# Standalone_Kaleidoscope_8085_POWER_SUPPL.net
KiCad netlist of a schematic drawn in EAGLE
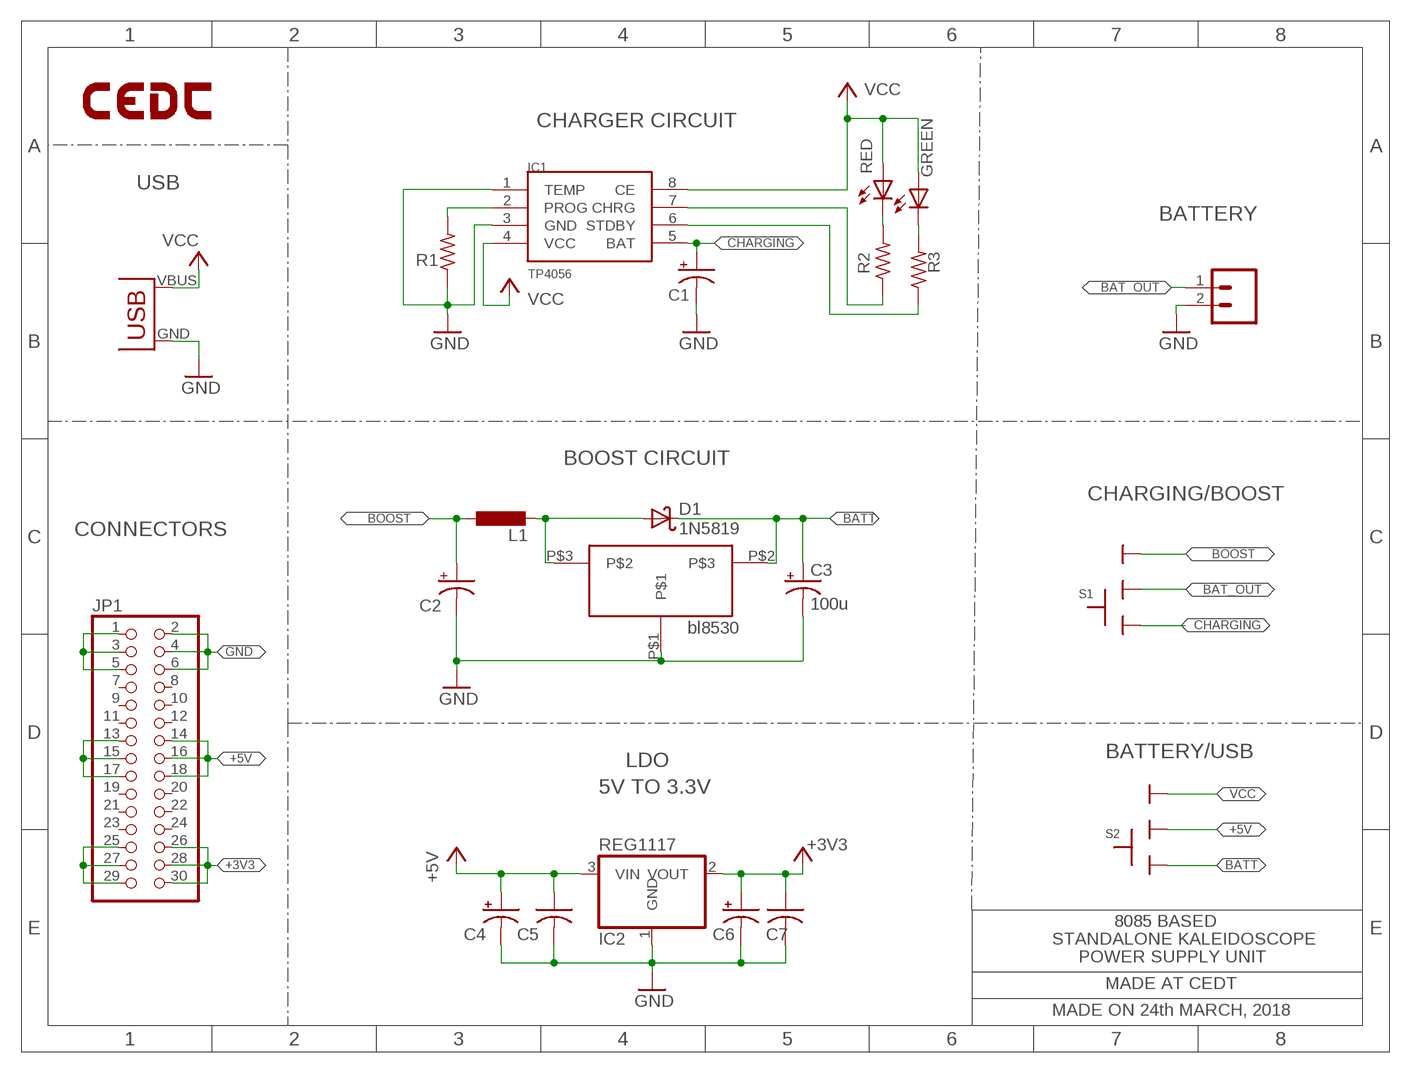
[diagram p0: schematic, sheet 1]

(export (version "E")
  (design (tool "Eeschema 10.0.6"))
  (components
    (comp (ref "BATTERY")
      (value "M02")
      (footprint "eagle-import:02P")
      (libsource (lib "eagle-import") (part "M02"))
    )
    (comp (ref "BL8530")
      (value "BL8530_5V")
      (footprint "eagle-import:BL8530_5V")
      (libsource (lib "eagle-import") (part "BL8530_5V"))
    )
    (comp (ref "C1")
      (value "10u")
      (footprint "eagle-import:C_6032-28R")
      (libsource (lib "eagle-import") (part "CAP_POL_10V"))
    )
    (comp (ref "C2")
      (value "10u")
      (footprint "eagle-import:C_6032-28R")
      (libsource (lib "eagle-import") (part "CAP_POL_10V"))
    )
    (comp (ref "C3")
      (value "100u")
      (footprint "eagle-import:C_6032-28R")
      (libsource (lib "eagle-import") (part "CEDT_JANUARY_2015_v7_CAP_POL_10V"))
    )
    (comp (ref "C4")
      (value "10u")
      (footprint "eagle-import:C_6032-28R")
      (libsource (lib "eagle-import") (part "CAP_POL_10V"))
    )
    (comp (ref "C5")
      (value "0.1u")
      (footprint "eagle-import:C0805")
      (libsource (lib "eagle-import") (part "CAP0805"))
    )
    (comp (ref "C6")
      (value "10u")
      (footprint "eagle-import:C_6032-28R")
      (libsource (lib "eagle-import") (part "CAP_POL_10V"))
    )
    (comp (ref "C7")
      (value "0.1u")
      (footprint "eagle-import:C0805")
      (libsource (lib "eagle-import") (part "CAP0805"))
    )
    (comp (ref "D1")
      (value "1N5819")
      (footprint "eagle-import:DO41-10")
      (libsource (lib "eagle-import") (part "1N5819"))
    )
    (comp (ref "GREEN")
      (value "LED3MM")
      (footprint "eagle-import:LED3MM")
      (libsource (lib "eagle-import") (part "LED3MM"))
    )
    (comp (ref "IC1")
      (value "TP4056")
      (footprint "eagle-import:SOP-8")
      (libsource (lib "eagle-import") (part "TP4056"))
    )
    (comp (ref "IC2")
      (value "REG1117")
      (footprint "eagle-import:SOT223")
      (libsource (lib "eagle-import") (part "REG1117"))
    )
    (comp (ref "JP1")
      (value "PINHD-2X15")
      (footprint "eagle-import:2X15")
      (libsource (lib "eagle-import") (part "PINHD-2X15"))
    )
    (comp (ref "L1")
      (value "47uH")
      (footprint "eagle-import:L4532P")
      (libsource (lib "eagle-import") (part "L-EUL4532P"))
    )
    (comp (ref "LOGO1")
      (value "LOGO-CEDTBOT-18MM")
      (footprint "eagle-import:LOGO-CEDT-BOT-18MM")
      (libsource (lib "eagle-import") (part "LOGO-CEDTBOT-18MM"))
    )
    (comp (ref "R1")
      (value "RESISTOR0805")
      (footprint "eagle-import:R0805")
      (libsource (lib "eagle-import") (part "RESISTOR0805"))
    )
    (comp (ref "R2")
      (value "470")
      (footprint "eagle-import:R0805")
      (libsource (lib "eagle-import") (part "RESISTOR0805"))
    )
    (comp (ref "R3")
      (value "470")
      (footprint "eagle-import:R0805")
      (libsource (lib "eagle-import") (part "RESISTOR0805"))
    )
    (comp (ref "RED")
      (value "LED3MM")
      (footprint "eagle-import:LED3MM")
      (libsource (lib "eagle-import") (part "LED3MM"))
    )
    (comp (ref "S1")
      (value "SLIDESWITCH-BIG")
      (footprint "eagle-import:BIGSWITCH")
      (libsource (lib "eagle-import") (part "SLIDESWITCH-BIG"))
    )
    (comp (ref "S2")
      (value "SLIDESWITCH-BIG")
      (footprint "eagle-import:BIGSWITCH")
      (libsource (lib "eagle-import") (part "SLIDESWITCH-BIG"))
    )
    (comp (ref "U$1")
      (value "USB(POWER)")
      (footprint "eagle-import:USB(POWER)")
      (libsource (lib "eagle-import") (part "USB(POWER)"))
    )
  )
  (nets
    (net (code "1") (name "+3V3") (class "Default")
      (node (ref "C6") (pin "+") (pinfunction "+_+") (pintype "passive"))
      (node (ref "C7") (pin "1") (pinfunction "1_1") (pintype "passive"))
      (node (ref "IC2") (pin "2") (pinfunction "VOUT_2") (pintype "output"))
      (node (ref "JP1") (pin "25") (pinfunction "25_25") (pintype "passive"))
      (node (ref "JP1") (pin "26") (pinfunction "26_26") (pintype "passive"))
      (node (ref "JP1") (pin "27") (pinfunction "27_27") (pintype "passive"))
      (node (ref "JP1") (pin "28") (pinfunction "28_28") (pintype "passive"))
      (node (ref "JP1") (pin "29") (pinfunction "29_29") (pintype "passive"))
      (node (ref "JP1") (pin "30") (pinfunction "30_30") (pintype "passive"))
    )
    (net (code "2") (name "+5V") (class "Default")
      (node (ref "C4") (pin "+") (pinfunction "+_+") (pintype "passive"))
      (node (ref "C5") (pin "1") (pinfunction "1_1") (pintype "passive"))
      (node (ref "IC2") (pin "3") (pinfunction "VIN_3") (pintype "input"))
      (node (ref "JP1") (pin "13") (pinfunction "13_13") (pintype "passive"))
      (node (ref "JP1") (pin "14") (pinfunction "14_14") (pintype "passive"))
      (node (ref "JP1") (pin "15") (pinfunction "15_15") (pintype "passive"))
      (node (ref "JP1") (pin "16") (pinfunction "16_16") (pintype "passive"))
      (node (ref "JP1") (pin "17") (pinfunction "17_17") (pintype "passive"))
      (node (ref "JP1") (pin "18") (pinfunction "18_18") (pintype "passive"))
      (node (ref "S2") (pin "2") (pinfunction "2_2") (pintype "bidirectional"))
    )
    (net (code "3") (name "/BATT") (class "Default")
      (node (ref "BL8530") (pin "P$2") (pinfunction "P$3_P$2") (pintype "bidirectional"))
      (node (ref "C3") (pin "+") (pinfunction "+_+") (pintype "passive"))
      (node (ref "D1") (pin "C") (pinfunction "C_C") (pintype "passive"))
      (node (ref "S2") (pin "1") (pinfunction "1_1") (pintype "bidirectional"))
    )
    (net (code "4") (name "/BAT_OUT") (class "Default")
      (node (ref "BATTERY") (pin "1") (pinfunction "1_1") (pintype "passive"))
      (node (ref "S1") (pin "2") (pinfunction "2_2") (pintype "bidirectional"))
    )
    (net (code "5") (name "/BOOST") (class "Default")
      (node (ref "C2") (pin "+") (pinfunction "+_+") (pintype "passive"))
      (node (ref "L1") (pin "1") (pinfunction "1_1") (pintype "passive"))
      (node (ref "S1") (pin "3") (pinfunction "3_3") (pintype "bidirectional"))
    )
    (net (code "6") (name "/CHARGING") (class "Default")
      (node (ref "C1") (pin "+") (pinfunction "+_+") (pintype "passive"))
      (node (ref "IC1") (pin "5") (pinfunction "BAT_5") (pintype "bidirectional"))
      (node (ref "S1") (pin "1") (pinfunction "1_1") (pintype "bidirectional"))
    )
    (net (code "7") (name "GND") (class "Default")
      (node (ref "BATTERY") (pin "2") (pinfunction "2_2") (pintype "passive"))
      (node (ref "BL8530") (pin "P$1") (pinfunction "P$1_P$1") (pintype "bidirectional"))
      (node (ref "C1") (pin "-") (pinfunction "-_-") (pintype "passive"))
      (node (ref "C2") (pin "-") (pinfunction "-_-") (pintype "passive"))
      (node (ref "C3") (pin "-") (pinfunction "-_-") (pintype "passive"))
      (node (ref "C4") (pin "-") (pinfunction "-_-") (pintype "passive"))
      (node (ref "C5") (pin "2") (pinfunction "2_2") (pintype "passive"))
      (node (ref "C6") (pin "-") (pinfunction "-_-") (pintype "passive"))
      (node (ref "C7") (pin "2") (pinfunction "2_2") (pintype "passive"))
      (node (ref "IC1") (pin "1") (pinfunction "TEMP_1") (pintype "bidirectional"))
      (node (ref "IC1") (pin "3") (pinfunction "GND_3") (pintype "bidirectional"))
      (node (ref "IC2") (pin "1") (pinfunction "GND_1") (pintype "power_in"))
      (node (ref "JP1") (pin "1") (pinfunction "1_1") (pintype "passive"))
      (node (ref "JP1") (pin "2") (pinfunction "2_2") (pintype "passive"))
      (node (ref "JP1") (pin "3") (pinfunction "3_3") (pintype "passive"))
      (node (ref "JP1") (pin "4") (pinfunction "4_4") (pintype "passive"))
      (node (ref "JP1") (pin "5") (pinfunction "5_5") (pintype "passive"))
      (node (ref "JP1") (pin "6") (pinfunction "6_6") (pintype "passive"))
      (node (ref "R1") (pin "1") (pinfunction "1_1") (pintype "passive"))
      (node (ref "U$1") (pin "GND") (pinfunction "GND_GND") (pintype "power_in"))
    )
    (net (code "8") (name "Net-(BL8530-P$2)") (class "Default")
      (node (ref "BL8530") (pin "P$3") (pinfunction "P$2_P$3") (pintype "bidirectional"))
      (node (ref "D1") (pin "A") (pinfunction "A_A") (pintype "passive"))
      (node (ref "L1") (pin "2") (pinfunction "2_2") (pintype "passive"))
    )
    (net (code "9") (name "Net-(GREEN-C)") (class "Default")
      (node (ref "GREEN") (pin "K") (pinfunction "C_K") (pintype "passive"))
      (node (ref "R3") (pin "2") (pinfunction "2_2") (pintype "passive"))
    )
    (net (code "10") (name "Net-(IC1-CHRG)") (class "Default")
      (node (ref "IC1") (pin "7") (pinfunction "CHRG_7") (pintype "bidirectional"))
      (node (ref "R2") (pin "1") (pinfunction "1_1") (pintype "passive"))
    )
    (net (code "11") (name "Net-(IC1-PROG)") (class "Default")
      (node (ref "IC1") (pin "2") (pinfunction "PROG_2") (pintype "bidirectional"))
      (node (ref "R1") (pin "2") (pinfunction "2_2") (pintype "passive"))
    )
    (net (code "12") (name "Net-(IC1-STDBY)") (class "Default")
      (node (ref "IC1") (pin "6") (pinfunction "STDBY_6") (pintype "bidirectional"))
      (node (ref "R3") (pin "1") (pinfunction "1_1") (pintype "passive"))
    )
    (net (code "13") (name "Net-(RED-C)") (class "Default")
      (node (ref "R2") (pin "2") (pinfunction "2_2") (pintype "passive"))
      (node (ref "RED") (pin "K") (pinfunction "C_K") (pintype "passive"))
    )
    (net (code "14") (name "VCC") (class "Default")
      (node (ref "GREEN") (pin "A") (pinfunction "A_A") (pintype "passive"))
      (node (ref "IC1") (pin "4") (pinfunction "VCC_4") (pintype "bidirectional"))
      (node (ref "IC1") (pin "8") (pinfunction "CE_8") (pintype "bidirectional"))
      (node (ref "RED") (pin "A") (pinfunction "A_A") (pintype "passive"))
      (node (ref "S2") (pin "3") (pinfunction "3_3") (pintype "bidirectional"))
      (node (ref "U$1") (pin "VBUS") (pinfunction "VCC_VBUS") (pintype "power_in"))
    )
    (net (code "15") (name "unconnected-(JP1-Pad7)") (class "Default")
      (node (ref "JP1") (pin "7") (pinfunction "7_7") (pintype "passive"))
    )
    (net (code "16") (name "unconnected-(JP1-Pad8)") (class "Default")
      (node (ref "JP1") (pin "8") (pinfunction "8_8") (pintype "passive"))
    )
    (net (code "17") (name "unconnected-(JP1-Pad9)") (class "Default")
      (node (ref "JP1") (pin "9") (pinfunction "9_9") (pintype "passive"))
    )
    (net (code "18") (name "unconnected-(JP1-Pad10)") (class "Default")
      (node (ref "JP1") (pin "10") (pinfunction "10_10") (pintype "passive"))
    )
    (net (code "19") (name "unconnected-(JP1-Pad11)") (class "Default")
      (node (ref "JP1") (pin "11") (pinfunction "11_11") (pintype "passive"))
    )
    (net (code "20") (name "unconnected-(JP1-Pad12)") (class "Default")
      (node (ref "JP1") (pin "12") (pinfunction "12_12") (pintype "passive"))
    )
    (net (code "21") (name "unconnected-(JP1-Pad19)") (class "Default")
      (node (ref "JP1") (pin "19") (pinfunction "19_19") (pintype "passive"))
    )
    (net (code "22") (name "unconnected-(JP1-Pad20)") (class "Default")
      (node (ref "JP1") (pin "20") (pinfunction "20_20") (pintype "passive"))
    )
    (net (code "23") (name "unconnected-(JP1-Pad21)") (class "Default")
      (node (ref "JP1") (pin "21") (pinfunction "21_21") (pintype "passive"))
    )
    (net (code "24") (name "unconnected-(JP1-Pad22)") (class "Default")
      (node (ref "JP1") (pin "22") (pinfunction "22_22") (pintype "passive"))
    )
    (net (code "25") (name "unconnected-(JP1-Pad23)") (class "Default")
      (node (ref "JP1") (pin "23") (pinfunction "23_23") (pintype "passive"))
    )
    (net (code "26") (name "unconnected-(JP1-Pad24)") (class "Default")
      (node (ref "JP1") (pin "24") (pinfunction "24_24") (pintype "passive"))
    )
  )
)
